# HighCurrentFetGND.net
KiCad netlist of a schematic drawn in Altium Designer
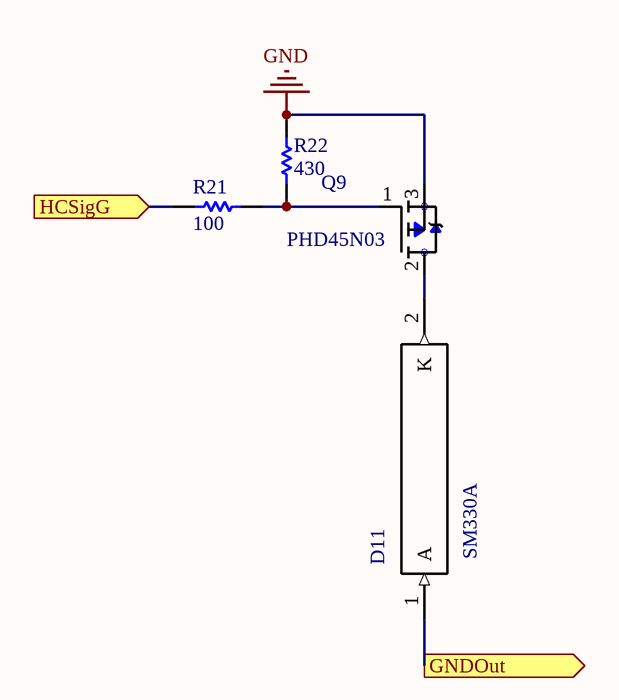
[diagram p0: HighCurrentFetGND.SchDoc]

(export (version "E")
  (design (tool "Eeschema 10.0.6"))
  (components
    (comp (ref "D11")
      (value "SM330A")
      (footprint "*DIOM5227X270N_S1M(Primary)")
      (description "SCHOTTKY RECTIFIER 2A; Voltage Vrrm: 60V; Diode Case Style: DO-214AC; Case Style: DO-214AC")
      (fields (field (name "MF") "STMicroelectronics") (field (name "MP") "STPS2L60A"))
      (libsource (lib "STPS2L60A") (part "STPS2L60A"))
    )
    (comp (ref "Q9")
      (value "PHD45N03")
      (footprint "*DPAK228P998X235-3N")
      (description "P-Channel 40 V 10.6 mOhm OptiMOSآ®-P2 Power-Transistor -PG-TO-252-3")
      (fields (field (name "MP") "IPD50P04P4L-11") (field (name "MF") "Infineon Technologies"))
      (libsource (lib "IPD50P04P4L-11") (part "IPD50P04P4L-11"))
    )
    (comp (ref "R21")
      (value "100")
      (footprint "6-0805_L")
      (description "Resistor")
      (fields (field (name "Comment") "R100") (field (name "PUBLISHER") "Altium Limited"))
      (libsource (lib "Miscellaneous Devices") (part "Res1"))
    )
    (comp (ref "R22")
      (value "430")
      (footprint "6-0805_L")
      (description "Resistor")
      (fields (field (name "Comment") "R430") (field (name "PUBLISHER") "Altium Limited"))
      (libsource (lib "Miscellaneous Devices") (part "Res1"))
    )
  )
  (nets
    (net (code "1") (name "/GNDOut") (class "Default")
      (node (ref "D11") (pin "1") (pinfunction "A_1") (pintype "input"))
    )
    (net (code "2") (name "/HCSigG") (class "Default")
      (node (ref "R21") (pin "1") (pinfunction "1_1") (pintype "passive"))
    )
    (net (code "3") (name "GND") (class "Default")
      (node (ref "Q9") (pin "3") (pinfunction "S_3") (pintype "passive"))
      (node (ref "R22") (pin "1") (pinfunction "1_1") (pintype "passive"))
    )
    (net (code "4") (name "Net-(D11-K)") (class "Default")
      (node (ref "D11") (pin "2") (pinfunction "K_2") (pintype "output"))
      (node (ref "Q9") (pin "2") (pinfunction "D_2") (pintype "passive"))
    )
    (net (code "5") (name "Net-(Q9-G)") (class "Default")
      (node (ref "Q9") (pin "1") (pinfunction "G_1") (pintype "passive"))
      (node (ref "R21") (pin "2") (pinfunction "2_2") (pintype "passive"))
      (node (ref "R22") (pin "2") (pinfunction "2_2") (pintype "passive"))
    )
  )
)
